# TUGAS_DAY0.net
KiCad netlist of a schematic drawn in EAGLE
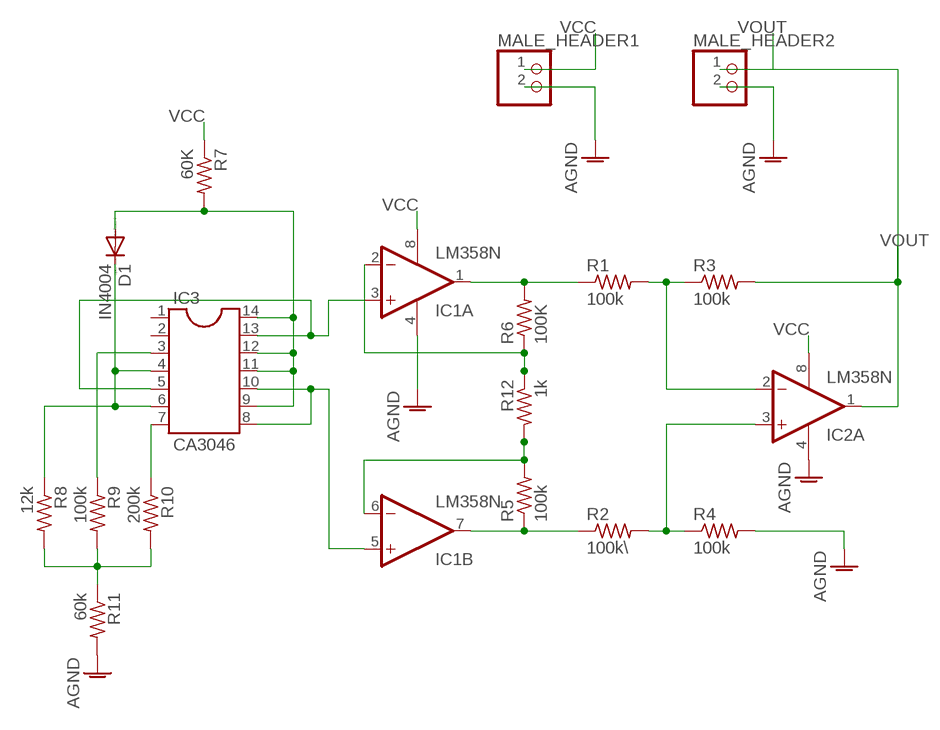
[diagram p0: schematic, sheet 1]

(export (version "E")
  (design (tool "Eeschema 10.0.6"))
  (components
    (comp (ref "D1")
      (value "IN4004")
      (footprint "eagle-import:D-7.5")
      (libsource (lib "eagle-import") (part "DIODE-D-7.5"))
    )
    (comp (ref "IC1")
      (value "LM358N")
      (footprint "eagle-import:DIL08")
      (libsource (lib "eagle-import") (part "LM358N"))
    )
    (comp (ref "IC2")
      (value "LM358N")
      (footprint "eagle-import:DIL08")
      (libsource (lib "eagle-import") (part "LM358N"))
    )
    (comp (ref "IC3")
      (value "CA3046")
      (footprint "eagle-import:DIL14")
      (libsource (lib "eagle-import") (part "DIL14"))
    )
    (comp (ref "MALE_HEADER1")
      (value "PINHD-1X2")
      (footprint "eagle-import:1X02")
      (libsource (lib "eagle-import") (part "PINHD-1X2"))
    )
    (comp (ref "MALE_HEADER2")
      (value "PINHD-1X2")
      (footprint "eagle-import:1X02")
      (libsource (lib "eagle-import") (part "PINHD-1X2"))
    )
    (comp (ref "R1")
      (value "100k")
      (footprint "eagle-import:0207_7")
      (libsource (lib "eagle-import") (part "R-US_0207/7"))
    )
    (comp (ref "R2")
      (value "100k\\")
      (footprint "eagle-import:0207_7")
      (libsource (lib "eagle-import") (part "R-US_0207/7"))
    )
    (comp (ref "R3")
      (value "100k")
      (footprint "eagle-import:0207_7")
      (libsource (lib "eagle-import") (part "R-US_0207/7"))
    )
    (comp (ref "R4")
      (value "100k")
      (footprint "eagle-import:0207_7")
      (libsource (lib "eagle-import") (part "R-US_0207/7"))
    )
    (comp (ref "R5")
      (value "100k")
      (footprint "eagle-import:0207_7")
      (libsource (lib "eagle-import") (part "R-US_0207/7"))
    )
    (comp (ref "R6")
      (value "100K")
      (footprint "eagle-import:0207_7")
      (libsource (lib "eagle-import") (part "R-US_0207/7"))
    )
    (comp (ref "R7")
      (value "60K")
      (footprint "eagle-import:0207_7")
      (libsource (lib "eagle-import") (part "R-US_0207/7"))
    )
    (comp (ref "R8")
      (value "12k")
      (footprint "eagle-import:0207_7")
      (libsource (lib "eagle-import") (part "R-US_0207/7"))
    )
    (comp (ref "R9")
      (value "100k")
      (footprint "eagle-import:0207_7")
      (libsource (lib "eagle-import") (part "R-US_0207/7"))
    )
    (comp (ref "R10")
      (value "200k")
      (footprint "eagle-import:0207_7")
      (libsource (lib "eagle-import") (part "R-US_0207/7"))
    )
    (comp (ref "R11")
      (value "60k")
      (footprint "eagle-import:0207_7")
      (libsource (lib "eagle-import") (part "R-US_0207/7"))
    )
    (comp (ref "R12")
      (value "1k")
      (footprint "eagle-import:0207_7")
      (libsource (lib "eagle-import") (part "R-US_0207/7"))
    )
  )
  (nets
    (net (code "1") (name "/VCC") (class "Default")
      (node (ref "IC1") (pin "8") (pinfunction "V+_8") (pintype "power_in"))
      (node (ref "IC2") (pin "8") (pinfunction "V+_8") (pintype "power_in"))
      (node (ref "MALE_HEADER1") (pin "1") (pinfunction "1_1") (pintype "passive"))
      (node (ref "R7") (pin "1") (pinfunction "1_1") (pintype "passive"))
    )
    (net (code "2") (name "/VOUT") (class "Default")
      (node (ref "IC2") (pin "1") (pinfunction "OUT_1") (pintype "output"))
      (node (ref "MALE_HEADER2") (pin "1") (pinfunction "1_1") (pintype "passive"))
      (node (ref "R3") (pin "2") (pinfunction "2_2") (pintype "passive"))
    )
    (net (code "3") (name "AGND") (class "Default")
      (node (ref "IC1") (pin "4") (pinfunction "V-_4") (pintype "power_in"))
      (node (ref "IC2") (pin "4") (pinfunction "V-_4") (pintype "power_in"))
      (node (ref "MALE_HEADER1") (pin "2") (pinfunction "2_2") (pintype "passive"))
      (node (ref "MALE_HEADER2") (pin "2") (pinfunction "2_2") (pintype "passive"))
      (node (ref "R11") (pin "2") (pinfunction "2_2") (pintype "passive"))
      (node (ref "R4") (pin "2") (pinfunction "2_2") (pintype "passive"))
    )
    (net (code "4") (name "Net-(D1-PadA)") (class "Default")
      (node (ref "D1") (pin "A") (pinfunction "A_A") (pintype "passive"))
      (node (ref "IC3") (pin "11") (pinfunction "11_11") (pintype "passive"))
      (node (ref "IC3") (pin "12") (pinfunction "12_12") (pintype "passive"))
      (node (ref "IC3") (pin "14") (pinfunction "14_14") (pintype "passive"))
      (node (ref "IC3") (pin "9") (pinfunction "9_9") (pintype "passive"))
      (node (ref "R7") (pin "2") (pinfunction "2_2") (pintype "passive"))
    )
    (net (code "5") (name "Net-(D1-PadC)") (class "Default")
      (node (ref "D1") (pin "C") (pinfunction "C_C") (pintype "passive"))
      (node (ref "IC3") (pin "4") (pinfunction "4_4") (pintype "passive"))
      (node (ref "IC3") (pin "6") (pinfunction "6_6") (pintype "passive"))
      (node (ref "R8") (pin "1") (pinfunction "1_1") (pintype "passive"))
    )
    (net (code "6") (name "Net-(IC1A-+IN)") (class "Default")
      (node (ref "IC1") (pin "3") (pinfunction "+IN_3") (pintype "input"))
      (node (ref "IC3") (pin "13") (pinfunction "13_13") (pintype "passive"))
      (node (ref "IC3") (pin "5") (pinfunction "5_5") (pintype "passive"))
    )
    (net (code "7") (name "Net-(IC1A--IN)") (class "Default")
      (node (ref "IC1") (pin "2") (pinfunction "-IN_2") (pintype "input"))
      (node (ref "R12") (pin "1") (pinfunction "1_1") (pintype "passive"))
      (node (ref "R6") (pin "1") (pinfunction "1_1") (pintype "passive"))
    )
    (net (code "8") (name "Net-(IC1A-OUT)") (class "Default")
      (node (ref "IC1") (pin "1") (pinfunction "OUT_1") (pintype "output"))
      (node (ref "R1") (pin "1") (pinfunction "1_1") (pintype "passive"))
      (node (ref "R6") (pin "2") (pinfunction "2_2") (pintype "passive"))
    )
    (net (code "9") (name "Net-(IC1B-+IN)") (class "Default")
      (node (ref "IC1") (pin "5") (pinfunction "+IN_5") (pintype "input"))
      (node (ref "IC3") (pin "10") (pinfunction "10_10") (pintype "passive"))
      (node (ref "IC3") (pin "8") (pinfunction "8_8") (pintype "passive"))
    )
    (net (code "10") (name "Net-(IC1B--IN)") (class "Default")
      (node (ref "IC1") (pin "6") (pinfunction "-IN_6") (pintype "input"))
      (node (ref "R12") (pin "2") (pinfunction "2_2") (pintype "passive"))
      (node (ref "R5") (pin "2") (pinfunction "2_2") (pintype "passive"))
    )
    (net (code "11") (name "Net-(IC1B-OUT)") (class "Default")
      (node (ref "IC1") (pin "7") (pinfunction "OUT_7") (pintype "output"))
      (node (ref "R2") (pin "1") (pinfunction "1_1") (pintype "passive"))
      (node (ref "R5") (pin "1") (pinfunction "1_1") (pintype "passive"))
    )
    (net (code "12") (name "Net-(IC2A-+IN)") (class "Default")
      (node (ref "IC2") (pin "3") (pinfunction "+IN_3") (pintype "input"))
      (node (ref "R2") (pin "2") (pinfunction "2_2") (pintype "passive"))
      (node (ref "R4") (pin "1") (pinfunction "1_1") (pintype "passive"))
    )
    (net (code "13") (name "Net-(IC2A--IN)") (class "Default")
      (node (ref "IC2") (pin "2") (pinfunction "-IN_2") (pintype "input"))
      (node (ref "R1") (pin "2") (pinfunction "2_2") (pintype "passive"))
      (node (ref "R3") (pin "1") (pinfunction "1_1") (pintype "passive"))
    )
    (net (code "14") (name "Net-(IC3-Pad3)") (class "Default")
      (node (ref "IC3") (pin "3") (pinfunction "3_3") (pintype "passive"))
      (node (ref "R9") (pin "1") (pinfunction "1_1") (pintype "passive"))
    )
    (net (code "15") (name "Net-(IC3-Pad7)") (class "Default")
      (node (ref "IC3") (pin "7") (pinfunction "7_7") (pintype "passive"))
      (node (ref "R10") (pin "1") (pinfunction "1_1") (pintype "passive"))
    )
    (net (code "16") (name "Net-(R10-Pad2)") (class "Default")
      (node (ref "R10") (pin "2") (pinfunction "2_2") (pintype "passive"))
      (node (ref "R11") (pin "1") (pinfunction "1_1") (pintype "passive"))
      (node (ref "R8") (pin "2") (pinfunction "2_2") (pintype "passive"))
      (node (ref "R9") (pin "2") (pinfunction "2_2") (pintype "passive"))
    )
    (net (code "17") (name "unconnected-(IC3-Pad1)") (class "Default")
      (node (ref "IC3") (pin "1") (pinfunction "1_1") (pintype "passive"))
    )
    (net (code "18") (name "unconnected-(IC3-Pad2)") (class "Default")
      (node (ref "IC3") (pin "2") (pinfunction "2_2") (pintype "passive"))
    )
  )
)
